# buttonpad.net
KiCad netlist of a schematic drawn in Altium Designer
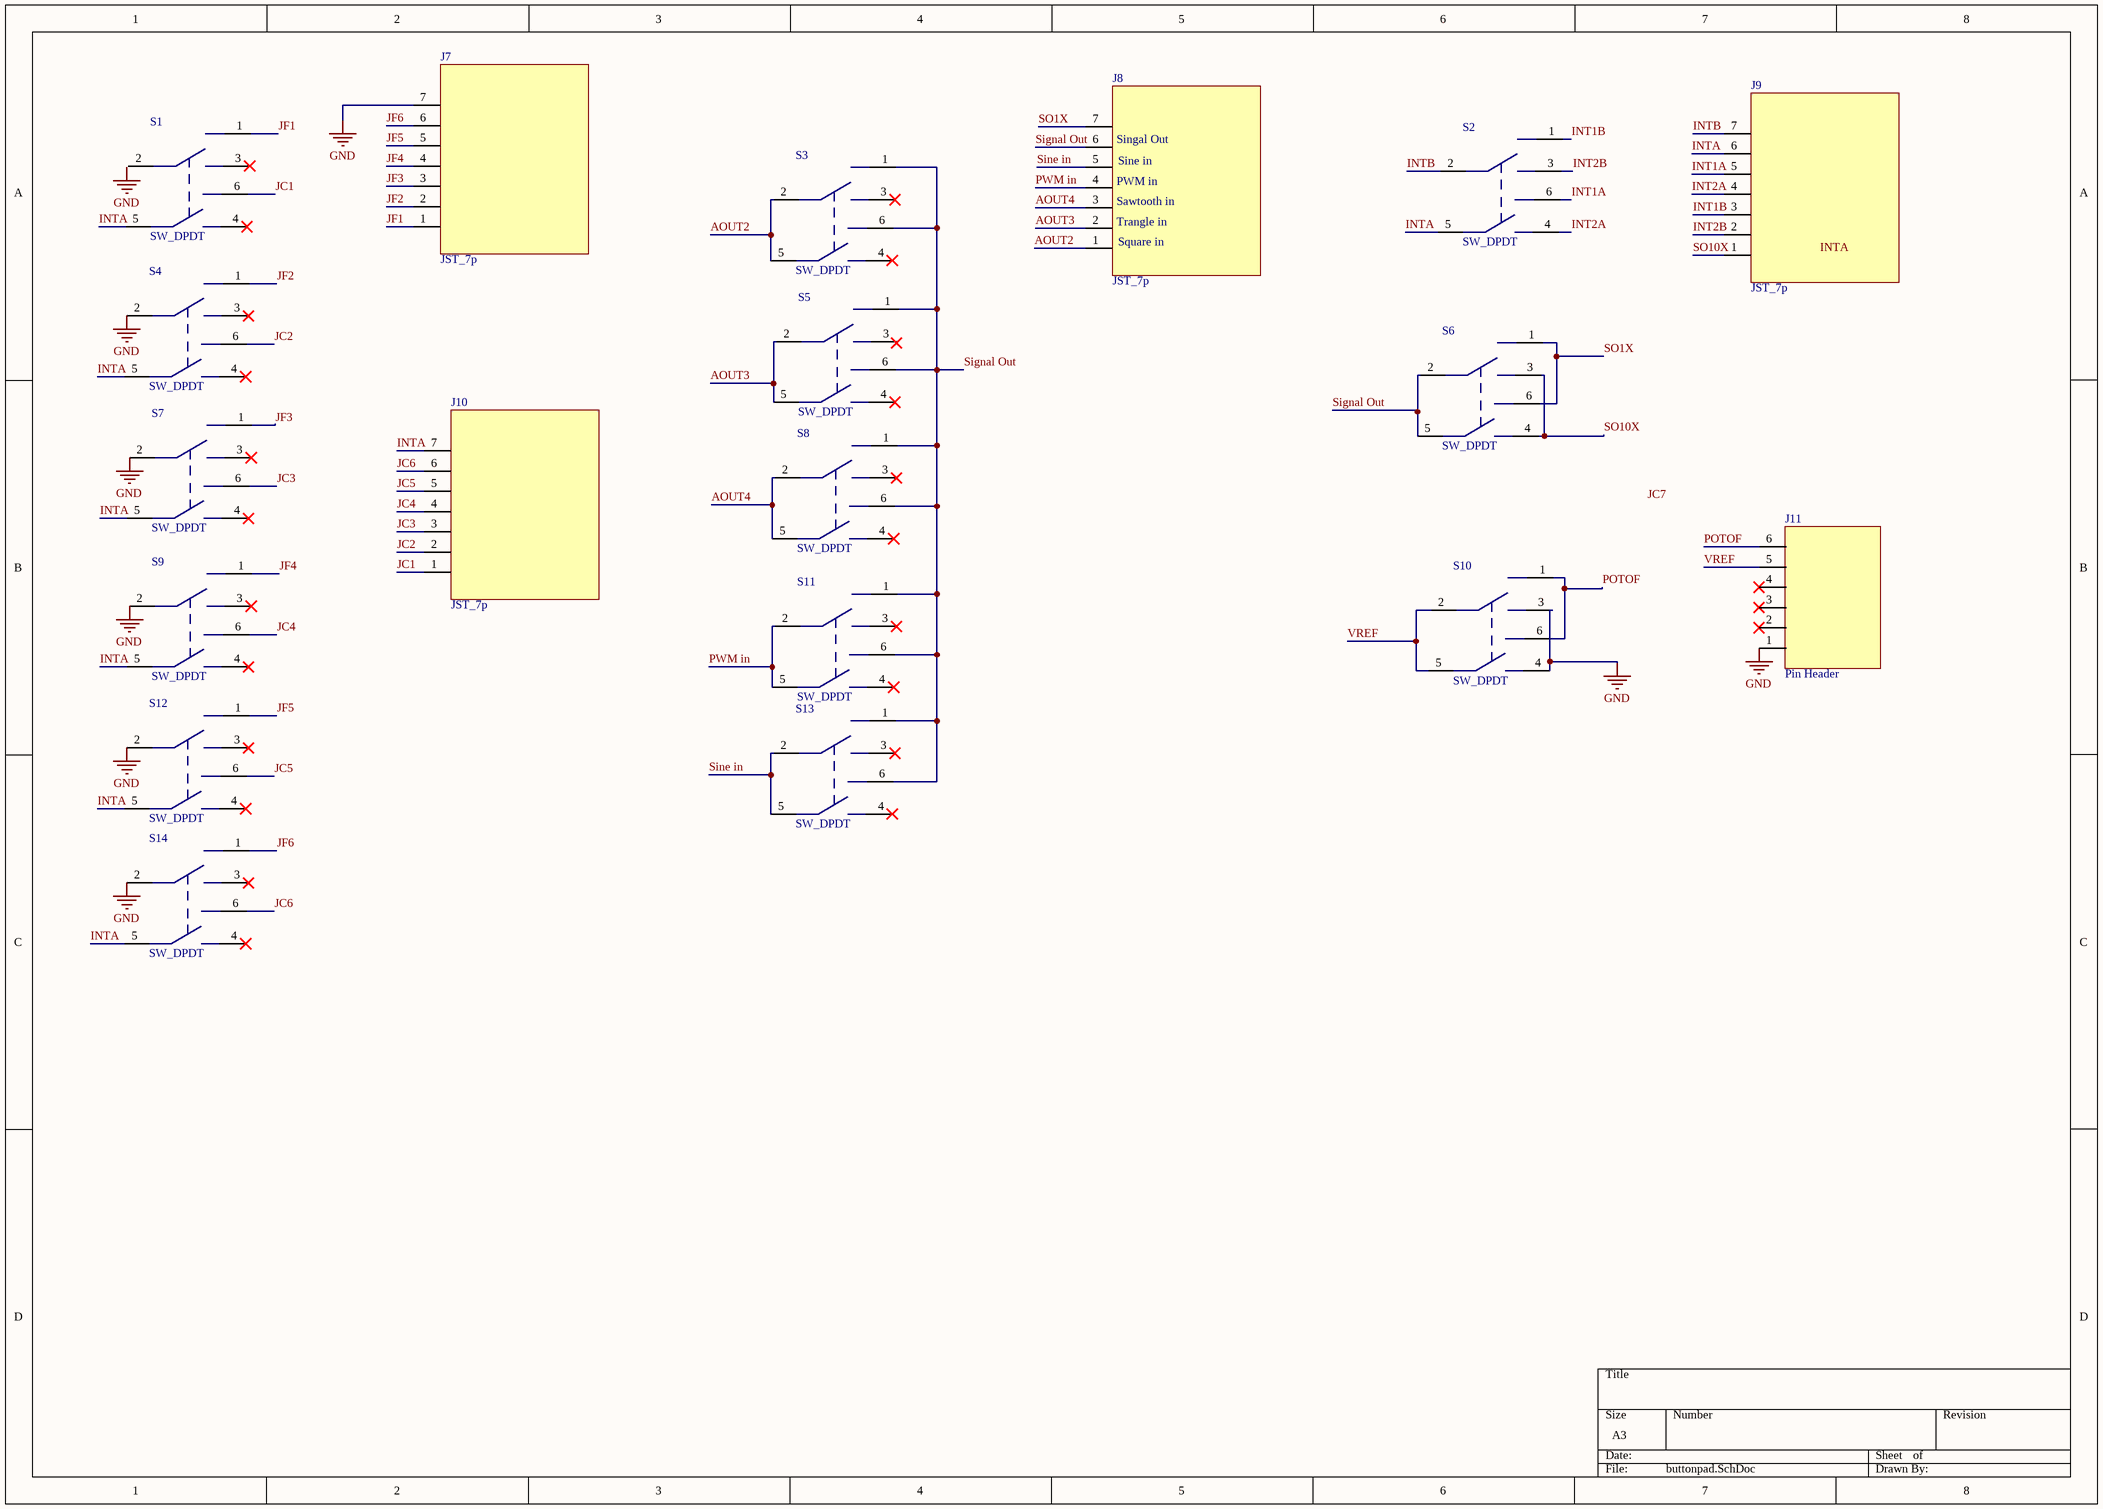
[diagram p0: buttonpad.SchDoc]

(export (version "E")
  (design (tool "Eeschema 10.0.6"))
  (components
    (comp (ref "J7") (value "JST_7p") (footprint "JST_7p") (libsource (lib "Funcgen") (part "JST_7p")))
    (comp (ref "J8") (value "JST_7p") (footprint "JST_7p") (libsource (lib "Funcgen") (part "JST_7p")))
    (comp (ref "J9") (value "JST_7p") (footprint "JST_7p") (libsource (lib "Funcgen") (part "JST_7p")))
    (comp (ref "J10") (value "JST_7p") (footprint "JST_7p") (libsource (lib "Funcgen") (part "JST_7p")))
    (comp (ref "J11") (value "Pin Header") (footprint "JST_6p") (libsource (lib "Schlib1") (part "JST_6p")))
    (comp (ref "S1") (value "SW_DPDT") (footprint "SW DPDT") (libsource (lib "Funcgen") (part "SW_DPDT")))
    (comp (ref "S2") (value "SW_DPDT") (footprint "SW DPDT") (libsource (lib "Funcgen") (part "SW_DPDT")))
    (comp (ref "S3") (value "SW_DPDT") (footprint "SW DPDT") (libsource (lib "Funcgen") (part "SW_DPDT")))
    (comp (ref "S4") (value "SW_DPDT") (footprint "SW DPDT") (libsource (lib "Funcgen") (part "SW_DPDT")))
    (comp (ref "S5") (value "SW_DPDT") (footprint "SW DPDT") (libsource (lib "Funcgen") (part "SW_DPDT")))
    (comp (ref "S6") (value "SW_DPDT") (footprint "SW DPDT") (libsource (lib "Funcgen") (part "SW_DPDT")))
    (comp (ref "S7") (value "SW_DPDT") (footprint "SW DPDT") (libsource (lib "Funcgen") (part "SW_DPDT")))
    (comp (ref "S8") (value "SW_DPDT") (footprint "SW DPDT") (libsource (lib "Funcgen") (part "SW_DPDT")))
    (comp (ref "S9") (value "SW_DPDT") (footprint "SW DPDT") (libsource (lib "Funcgen") (part "SW_DPDT")))
    (comp (ref "S10") (value "SW_DPDT") (footprint "SW DPDT") (libsource (lib "Funcgen") (part "SW_DPDT")))
    (comp (ref "S11") (value "SW_DPDT") (footprint "SW DPDT") (libsource (lib "Funcgen") (part "SW_DPDT")))
    (comp (ref "S12") (value "SW_DPDT") (footprint "SW DPDT") (libsource (lib "Funcgen") (part "SW_DPDT")))
    (comp (ref "S13") (value "SW_DPDT") (footprint "SW DPDT") (libsource (lib "Funcgen") (part "SW_DPDT")))
    (comp (ref "S14") (value "SW_DPDT") (footprint "SW DPDT") (libsource (lib "Funcgen") (part "SW_DPDT")))
  )
  (nets
    (net (code "1") (name "/AOUT2") (class "Default")
      (node (ref "J8") (pin "1") (pinfunction "1_1") (pintype "passive"))
      (node (ref "S3") (pin "2") (pinfunction "2_2") (pintype "passive"))
      (node (ref "S3") (pin "5") (pinfunction "5_5") (pintype "passive"))
    )
    (net (code "2") (name "/AOUT3") (class "Default")
      (node (ref "J8") (pin "2") (pinfunction "2_2") (pintype "passive"))
      (node (ref "S5") (pin "2") (pinfunction "2_2") (pintype "passive"))
      (node (ref "S5") (pin "5") (pinfunction "5_5") (pintype "passive"))
    )
    (net (code "3") (name "/AOUT4") (class "Default")
      (node (ref "J8") (pin "3") (pinfunction "3_3") (pintype "passive"))
      (node (ref "S8") (pin "2") (pinfunction "2_2") (pintype "passive"))
      (node (ref "S8") (pin "5") (pinfunction "5_5") (pintype "passive"))
    )
    (net (code "4") (name "/INT1A") (class "Default")
      (node (ref "J9") (pin "5") (pinfunction "5_5") (pintype "passive"))
      (node (ref "S2") (pin "6") (pinfunction "6_6") (pintype "passive"))
    )
    (net (code "5") (name "/INT1B") (class "Default")
      (node (ref "J9") (pin "3") (pinfunction "3_3") (pintype "passive"))
      (node (ref "S2") (pin "1") (pinfunction "1_1") (pintype "passive"))
    )
    (net (code "6") (name "/INT2A") (class "Default")
      (node (ref "J9") (pin "4") (pinfunction "4_4") (pintype "passive"))
      (node (ref "S2") (pin "4") (pinfunction "4_4") (pintype "passive"))
    )
    (net (code "7") (name "/INT2B") (class "Default")
      (node (ref "J9") (pin "2") (pinfunction "2_2") (pintype "passive"))
      (node (ref "S2") (pin "3") (pinfunction "3_3") (pintype "passive"))
    )
    (net (code "8") (name "/INTA") (class "Default")
      (node (ref "J10") (pin "7") (pinfunction "7_7") (pintype "passive"))
      (node (ref "J9") (pin "6") (pinfunction "6_6") (pintype "passive"))
      (node (ref "S1") (pin "5") (pinfunction "5_5") (pintype "passive"))
      (node (ref "S12") (pin "5") (pinfunction "5_5") (pintype "passive"))
      (node (ref "S14") (pin "5") (pinfunction "5_5") (pintype "passive"))
      (node (ref "S2") (pin "5") (pinfunction "5_5") (pintype "passive"))
      (node (ref "S4") (pin "5") (pinfunction "5_5") (pintype "passive"))
      (node (ref "S7") (pin "5") (pinfunction "5_5") (pintype "passive"))
      (node (ref "S9") (pin "5") (pinfunction "5_5") (pintype "passive"))
    )
    (net (code "9") (name "/INTB") (class "Default")
      (node (ref "J9") (pin "7") (pinfunction "7_7") (pintype "passive"))
      (node (ref "S2") (pin "2") (pinfunction "2_2") (pintype "passive"))
    )
    (net (code "10") (name "/JC1") (class "Default")
      (node (ref "J10") (pin "1") (pinfunction "1_1") (pintype "passive"))
      (node (ref "S1") (pin "6") (pinfunction "6_6") (pintype "passive"))
    )
    (net (code "11") (name "/JC2") (class "Default")
      (node (ref "J10") (pin "2") (pinfunction "2_2") (pintype "passive"))
      (node (ref "S4") (pin "6") (pinfunction "6_6") (pintype "passive"))
    )
    (net (code "12") (name "/JC3") (class "Default")
      (node (ref "J10") (pin "3") (pinfunction "3_3") (pintype "passive"))
      (node (ref "S7") (pin "6") (pinfunction "6_6") (pintype "passive"))
    )
    (net (code "13") (name "/JC4") (class "Default")
      (node (ref "J10") (pin "4") (pinfunction "4_4") (pintype "passive"))
      (node (ref "S9") (pin "6") (pinfunction "6_6") (pintype "passive"))
    )
    (net (code "14") (name "/JC5") (class "Default")
      (node (ref "J10") (pin "5") (pinfunction "5_5") (pintype "passive"))
      (node (ref "S12") (pin "6") (pinfunction "6_6") (pintype "passive"))
    )
    (net (code "15") (name "/JC6") (class "Default")
      (node (ref "J10") (pin "6") (pinfunction "6_6") (pintype "passive"))
      (node (ref "S14") (pin "6") (pinfunction "6_6") (pintype "passive"))
    )
    (net (code "17") (name "/JF1") (class "Default")
      (node (ref "J7") (pin "1") (pinfunction "1_1") (pintype "passive"))
      (node (ref "S1") (pin "1") (pinfunction "1_1") (pintype "passive"))
    )
    (net (code "18") (name "/JF2") (class "Default")
      (node (ref "J7") (pin "2") (pinfunction "2_2") (pintype "passive"))
      (node (ref "S4") (pin "1") (pinfunction "1_1") (pintype "passive"))
    )
    (net (code "19") (name "/JF3") (class "Default")
      (node (ref "J7") (pin "3") (pinfunction "3_3") (pintype "passive"))
      (node (ref "S7") (pin "1") (pinfunction "1_1") (pintype "passive"))
    )
    (net (code "20") (name "/JF4") (class "Default")
      (node (ref "J7") (pin "4") (pinfunction "4_4") (pintype "passive"))
      (node (ref "S9") (pin "1") (pinfunction "1_1") (pintype "passive"))
    )
    (net (code "21") (name "/JF5") (class "Default")
      (node (ref "J7") (pin "5") (pinfunction "5_5") (pintype "passive"))
      (node (ref "S12") (pin "1") (pinfunction "1_1") (pintype "passive"))
    )
    (net (code "22") (name "/JF6") (class "Default")
      (node (ref "J7") (pin "6") (pinfunction "6_6") (pintype "passive"))
      (node (ref "S14") (pin "1") (pinfunction "1_1") (pintype "passive"))
    )
    (net (code "23") (name "/POTOF") (class "Default")
      (node (ref "J11") (pin "6") (pinfunction "6_6") (pintype "passive"))
      (node (ref "S10") (pin "1") (pinfunction "1_1") (pintype "passive"))
      (node (ref "S10") (pin "6") (pinfunction "6_6") (pintype "passive"))
    )
    (net (code "24") (name "/PWM in") (class "Default")
      (node (ref "J8") (pin "4") (pinfunction "4_4") (pintype "passive"))
      (node (ref "S11") (pin "2") (pinfunction "2_2") (pintype "passive"))
      (node (ref "S11") (pin "5") (pinfunction "5_5") (pintype "passive"))
    )
    (net (code "25") (name "/SO1X") (class "Default")
      (node (ref "J8") (pin "7") (pinfunction "7_7") (pintype "passive"))
      (node (ref "S6") (pin "1") (pinfunction "1_1") (pintype "passive"))
      (node (ref "S6") (pin "6") (pinfunction "6_6") (pintype "passive"))
    )
    (net (code "26") (name "/SO10X") (class "Default")
      (node (ref "J9") (pin "1") (pinfunction "1_1") (pintype "passive"))
      (node (ref "S6") (pin "3") (pinfunction "3_3") (pintype "passive"))
      (node (ref "S6") (pin "4") (pinfunction "4_4") (pintype "passive"))
    )
    (net (code "27") (name "/Signal Out") (class "Default")
      (node (ref "J8") (pin "6") (pinfunction "6_6") (pintype "passive"))
      (node (ref "S11") (pin "1") (pinfunction "1_1") (pintype "passive"))
      (node (ref "S11") (pin "6") (pinfunction "6_6") (pintype "passive"))
      (node (ref "S13") (pin "1") (pinfunction "1_1") (pintype "passive"))
      (node (ref "S13") (pin "6") (pinfunction "6_6") (pintype "passive"))
      (node (ref "S3") (pin "1") (pinfunction "1_1") (pintype "passive"))
      (node (ref "S3") (pin "6") (pinfunction "6_6") (pintype "passive"))
      (node (ref "S5") (pin "1") (pinfunction "1_1") (pintype "passive"))
      (node (ref "S5") (pin "6") (pinfunction "6_6") (pintype "passive"))
      (node (ref "S6") (pin "2") (pinfunction "2_2") (pintype "passive"))
      (node (ref "S6") (pin "5") (pinfunction "5_5") (pintype "passive"))
      (node (ref "S8") (pin "1") (pinfunction "1_1") (pintype "passive"))
      (node (ref "S8") (pin "6") (pinfunction "6_6") (pintype "passive"))
    )
    (net (code "28") (name "/Sine in") (class "Default")
      (node (ref "J8") (pin "5") (pinfunction "5_5") (pintype "passive"))
      (node (ref "S13") (pin "2") (pinfunction "2_2") (pintype "passive"))
      (node (ref "S13") (pin "5") (pinfunction "5_5") (pintype "passive"))
    )
    (net (code "29") (name "/VREF") (class "Default")
      (node (ref "J11") (pin "5") (pinfunction "5_5") (pintype "passive"))
      (node (ref "S10") (pin "2") (pinfunction "2_2") (pintype "passive"))
      (node (ref "S10") (pin "5") (pinfunction "5_5") (pintype "passive"))
    )
    (net (code "30") (name "GND") (class "Default")
      (node (ref "J11") (pin "1") (pinfunction "1_1") (pintype "passive"))
      (node (ref "J7") (pin "7") (pinfunction "7_7") (pintype "passive"))
      (node (ref "S10") (pin "3") (pinfunction "3_3") (pintype "passive"))
      (node (ref "S10") (pin "4") (pinfunction "4_4") (pintype "passive"))
      (node (ref "S12") (pin "2") (pinfunction "2_2") (pintype "passive"))
      (node (ref "S14") (pin "2") (pinfunction "2_2") (pintype "passive"))
      (node (ref "S4") (pin "2") (pinfunction "2_2") (pintype "passive"))
      (node (ref "S7") (pin "2") (pinfunction "2_2") (pintype "passive"))
      (node (ref "S9") (pin "2") (pinfunction "2_2") (pintype "passive"))
    )
    (net (code "31") (name "unconnected-(J11-Pad2)") (class "Default")
      (node (ref "J11") (pin "2") (pinfunction "2_2") (pintype "passive+no_connect"))
    )
    (net (code "32") (name "unconnected-(J11-Pad3)") (class "Default")
      (node (ref "J11") (pin "3") (pinfunction "3_3") (pintype "passive+no_connect"))
    )
    (net (code "33") (name "unconnected-(J11-Pad4)") (class "Default")
      (node (ref "J11") (pin "4") (pinfunction "4_4") (pintype "passive+no_connect"))
    )
    (net (code "34") (name "unconnected-(S1-Pad2)") (class "Default")
      (node (ref "S1") (pin "2") (pinfunction "2_2") (pintype "passive"))
    )
    (net (code "35") (name "unconnected-(S1-Pad3)") (class "Default")
      (node (ref "S1") (pin "3") (pinfunction "3_3") (pintype "passive+no_connect"))
    )
    (net (code "36") (name "unconnected-(S1-Pad4)") (class "Default")
      (node (ref "S1") (pin "4") (pinfunction "4_4") (pintype "passive+no_connect"))
    )
    (net (code "37") (name "unconnected-(S3-Pad3)") (class "Default")
      (node (ref "S3") (pin "3") (pinfunction "3_3") (pintype "passive+no_connect"))
    )
    (net (code "38") (name "unconnected-(S3-Pad4)") (class "Default")
      (node (ref "S3") (pin "4") (pinfunction "4_4") (pintype "passive+no_connect"))
    )
    (net (code "39") (name "unconnected-(S4-Pad3)") (class "Default")
      (node (ref "S4") (pin "3") (pinfunction "3_3") (pintype "passive+no_connect"))
    )
    (net (code "40") (name "unconnected-(S4-Pad4)") (class "Default")
      (node (ref "S4") (pin "4") (pinfunction "4_4") (pintype "passive+no_connect"))
    )
    (net (code "41") (name "unconnected-(S5-Pad3)") (class "Default")
      (node (ref "S5") (pin "3") (pinfunction "3_3") (pintype "passive"))
    )
    (net (code "42") (name "unconnected-(S5-Pad4)") (class "Default")
      (node (ref "S5") (pin "4") (pinfunction "4_4") (pintype "passive+no_connect"))
    )
    (net (code "43") (name "unconnected-(S7-Pad3)") (class "Default")
      (node (ref "S7") (pin "3") (pinfunction "3_3") (pintype "passive+no_connect"))
    )
    (net (code "44") (name "unconnected-(S7-Pad4)") (class "Default")
      (node (ref "S7") (pin "4") (pinfunction "4_4") (pintype "passive+no_connect"))
    )
    (net (code "45") (name "unconnected-(S8-Pad3)") (class "Default")
      (node (ref "S8") (pin "3") (pinfunction "3_3") (pintype "passive+no_connect"))
    )
    (net (code "46") (name "unconnected-(S8-Pad4)") (class "Default")
      (node (ref "S8") (pin "4") (pinfunction "4_4") (pintype "passive+no_connect"))
    )
    (net (code "47") (name "unconnected-(S9-Pad3)") (class "Default")
      (node (ref "S9") (pin "3") (pinfunction "3_3") (pintype "passive+no_connect"))
    )
    (net (code "48") (name "unconnected-(S9-Pad4)") (class "Default")
      (node (ref "S9") (pin "4") (pinfunction "4_4") (pintype "passive+no_connect"))
    )
    (net (code "49") (name "unconnected-(S11-Pad3)") (class "Default")
      (node (ref "S11") (pin "3") (pinfunction "3_3") (pintype "passive+no_connect"))
    )
    (net (code "50") (name "unconnected-(S11-Pad4)") (class "Default")
      (node (ref "S11") (pin "4") (pinfunction "4_4") (pintype "passive+no_connect"))
    )
    (net (code "51") (name "unconnected-(S12-Pad3)") (class "Default")
      (node (ref "S12") (pin "3") (pinfunction "3_3") (pintype "passive+no_connect"))
    )
    (net (code "52") (name "unconnected-(S12-Pad4)") (class "Default")
      (node (ref "S12") (pin "4") (pinfunction "4_4") (pintype "passive+no_connect"))
    )
    (net (code "53") (name "unconnected-(S13-Pad3)") (class "Default")
      (node (ref "S13") (pin "3") (pinfunction "3_3") (pintype "passive+no_connect"))
    )
    (net (code "54") (name "unconnected-(S13-Pad4)") (class "Default")
      (node (ref "S13") (pin "4") (pinfunction "4_4") (pintype "passive+no_connect"))
    )
    (net (code "55") (name "unconnected-(S14-Pad3)") (class "Default")
      (node (ref "S14") (pin "3") (pinfunction "3_3") (pintype "passive+no_connect"))
    )
    (net (code "56") (name "unconnected-(S14-Pad4)") (class "Default")
      (node (ref "S14") (pin "4") (pinfunction "4_4") (pintype "passive+no_connect"))
    )
  )
)
